# konekobit-001.net
KiCad netlist of a schematic drawn in EAGLE
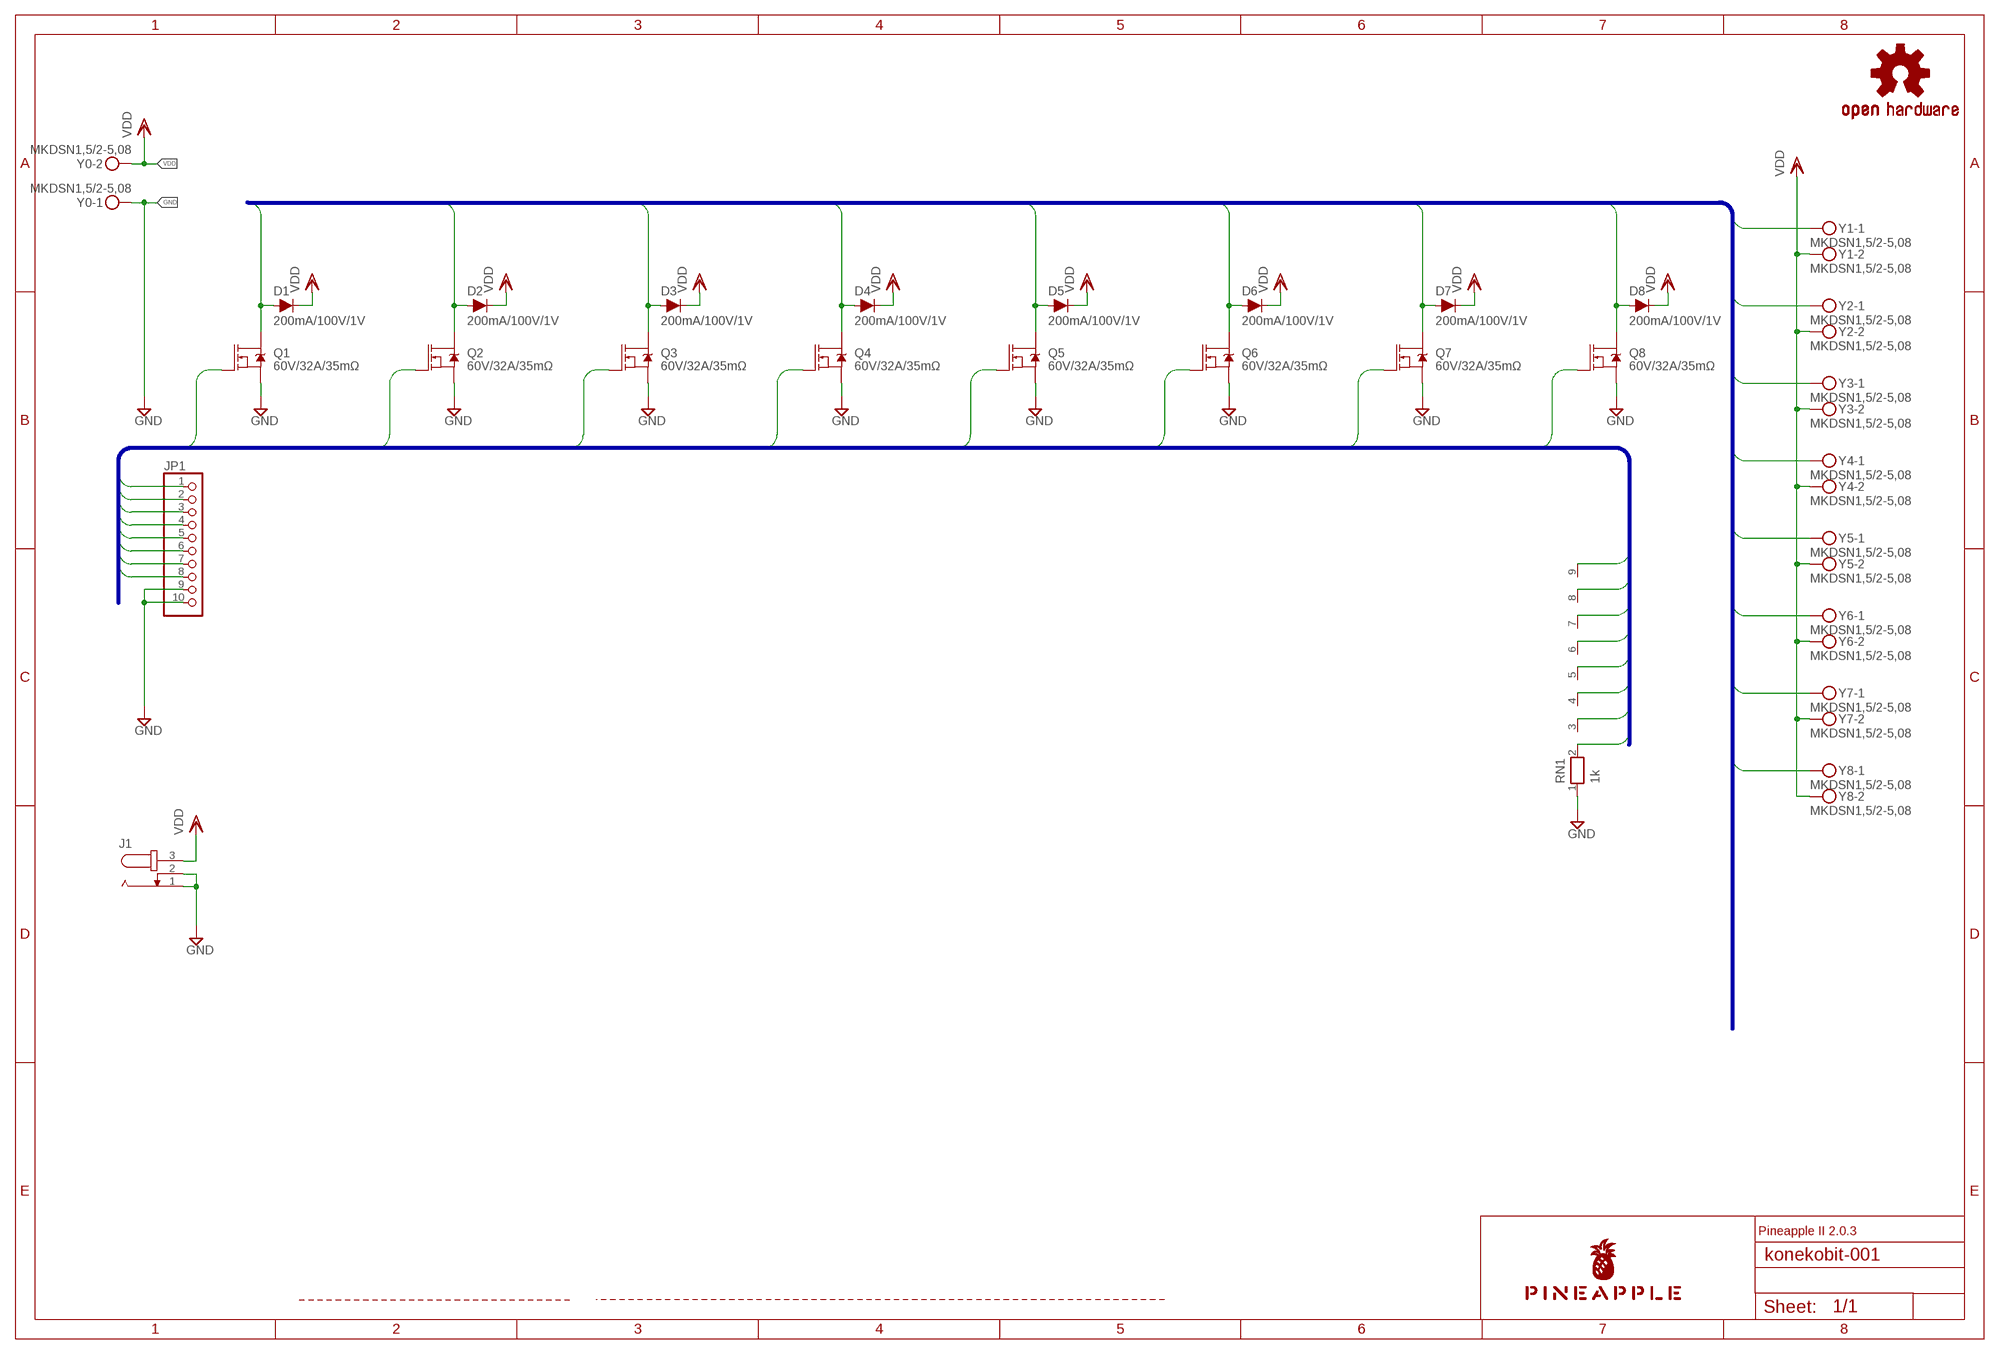
[diagram p0: schematic, sheet 1]

(export (version "E")
  (design (tool "Eeschema 10.0.6"))
  (components
    (comp (ref "D1")
      (value "200mA/100V/1V")
      (footprint "eagle-import:DIODE-1N4148")
      (libsource (lib "eagle-import") (part "DIODE-1N4148"))
    )
    (comp (ref "D2")
      (value "200mA/100V/1V")
      (footprint "eagle-import:DIODE-1N4148")
      (libsource (lib "eagle-import") (part "DIODE-1N4148"))
    )
    (comp (ref "D3")
      (value "200mA/100V/1V")
      (footprint "eagle-import:DIODE-1N4148")
      (libsource (lib "eagle-import") (part "DIODE-1N4148"))
    )
    (comp (ref "D4")
      (value "200mA/100V/1V")
      (footprint "eagle-import:DIODE-1N4148")
      (libsource (lib "eagle-import") (part "DIODE-1N4148"))
    )
    (comp (ref "D5")
      (value "200mA/100V/1V")
      (footprint "eagle-import:DIODE-1N4148")
      (libsource (lib "eagle-import") (part "DIODE-1N4148"))
    )
    (comp (ref "D6")
      (value "200mA/100V/1V")
      (footprint "eagle-import:DIODE-1N4148")
      (libsource (lib "eagle-import") (part "DIODE-1N4148"))
    )
    (comp (ref "D7")
      (value "200mA/100V/1V")
      (footprint "eagle-import:DIODE-1N4148")
      (libsource (lib "eagle-import") (part "DIODE-1N4148"))
    )
    (comp (ref "D8")
      (value "200mA/100V/1V")
      (footprint "eagle-import:DIODE-1N4148")
      (libsource (lib "eagle-import") (part "DIODE-1N4148"))
    )
    (comp (ref "J1")
      (value "JACK-PLUG0")
      (footprint "eagle-import:SPC4077")
      (libsource (lib "eagle-import") (part "JACK-PLUG0"))
    )
    (comp (ref "JP1")
      (value "PINHD-1X10")
      (footprint "eagle-import:1X10")
      (libsource (lib "eagle-import") (part "PINHD-1X10"))
    )
    (comp (ref "LOGO1")
      (value "OSHW-LOGOS-COPPER")
      (footprint "eagle-import:OSHW-LOGO-S_COPPER")
      (libsource (lib "eagle-import") (part "OSHW-LOGOS-COPPER"))
    )
    (comp (ref "Q1")
      (value "60V/32A/35mΩ")
      (footprint "eagle-import:TO220V")
      (libsource (lib "eagle-import") (part "MOSFET-NCH-FQP30N06L"))
    )
    (comp (ref "Q2")
      (value "60V/32A/35mΩ")
      (footprint "eagle-import:TO220V")
      (libsource (lib "eagle-import") (part "MOSFET-NCH-FQP30N06L"))
    )
    (comp (ref "Q3")
      (value "60V/32A/35mΩ")
      (footprint "eagle-import:TO220V")
      (libsource (lib "eagle-import") (part "MOSFET-NCH-FQP30N06L"))
    )
    (comp (ref "Q4")
      (value "60V/32A/35mΩ")
      (footprint "eagle-import:TO220V")
      (libsource (lib "eagle-import") (part "MOSFET-NCH-FQP30N06L"))
    )
    (comp (ref "Q5")
      (value "60V/32A/35mΩ")
      (footprint "eagle-import:TO220V")
      (libsource (lib "eagle-import") (part "MOSFET-NCH-FQP30N06L"))
    )
    (comp (ref "Q6")
      (value "60V/32A/35mΩ")
      (footprint "eagle-import:TO220V")
      (libsource (lib "eagle-import") (part "MOSFET-NCH-FQP30N06L"))
    )
    (comp (ref "Q7")
      (value "60V/32A/35mΩ")
      (footprint "eagle-import:TO220V")
      (libsource (lib "eagle-import") (part "MOSFET-NCH-FQP30N06L"))
    )
    (comp (ref "Q8")
      (value "60V/32A/35mΩ")
      (footprint "eagle-import:TO220V")
      (libsource (lib "eagle-import") (part "MOSFET-NCH-FQP30N06L"))
    )
    (comp (ref "RN1")
      (value "1k")
      (footprint "eagle-import:RN-9")
      (libsource (lib "eagle-import") (part "RN08"))
    )
    (comp (ref "U$1")
      (value "PINEAPPLE450_SILK")
      (footprint "eagle-import:PINEAPPLE450_SILK")
      (libsource (lib "eagle-import") (part "PINEAPPLE450_SILK"))
    )
    (comp (ref "Y0")
      (value "MKDSN1,5/2-5,08")
      (footprint "eagle-import:MKDSN1,5_2-5,08")
      (libsource (lib "eagle-import") (part "MKDSN1,5/2-5,08"))
    )
    (comp (ref "Y1")
      (value "MKDSN1,5/2-5,08")
      (footprint "eagle-import:MKDSN1,5_2-5,08")
      (libsource (lib "eagle-import") (part "MKDSN1,5/2-5,08"))
    )
    (comp (ref "Y2")
      (value "MKDSN1,5/2-5,08")
      (footprint "eagle-import:MKDSN1,5_2-5,08")
      (libsource (lib "eagle-import") (part "MKDSN1,5/2-5,08"))
    )
    (comp (ref "Y3")
      (value "MKDSN1,5/2-5,08")
      (footprint "eagle-import:MKDSN1,5_2-5,08")
      (libsource (lib "eagle-import") (part "MKDSN1,5/2-5,08"))
    )
    (comp (ref "Y4")
      (value "MKDSN1,5/2-5,08")
      (footprint "eagle-import:MKDSN1,5_2-5,08")
      (libsource (lib "eagle-import") (part "MKDSN1,5/2-5,08"))
    )
    (comp (ref "Y5")
      (value "MKDSN1,5/2-5,08")
      (footprint "eagle-import:MKDSN1,5_2-5,08")
      (libsource (lib "eagle-import") (part "MKDSN1,5/2-5,08"))
    )
    (comp (ref "Y6")
      (value "MKDSN1,5/2-5,08")
      (footprint "eagle-import:MKDSN1,5_2-5,08")
      (libsource (lib "eagle-import") (part "MKDSN1,5/2-5,08"))
    )
    (comp (ref "Y7")
      (value "MKDSN1,5/2-5,08")
      (footprint "eagle-import:MKDSN1,5_2-5,08")
      (libsource (lib "eagle-import") (part "MKDSN1,5/2-5,08"))
    )
    (comp (ref "Y8")
      (value "MKDSN1,5/2-5,08")
      (footprint "eagle-import:MKDSN1,5_2-5,08")
      (libsource (lib "eagle-import") (part "MKDSN1,5/2-5,08"))
    )
  )
  (nets
    (net (code "1") (name "/DRAIN1") (class "Default")
      (node (ref "D1") (pin "A") (pinfunction "A_A") (pintype "passive"))
      (node (ref "Q1") (pin "2") (pinfunction "D_2") (pintype "bidirectional"))
      (node (ref "Y1") (pin "1") (pinfunction "KL_1") (pintype "passive"))
    )
    (net (code "2") (name "/DRAIN2") (class "Default")
      (node (ref "D2") (pin "A") (pinfunction "A_A") (pintype "passive"))
      (node (ref "Q2") (pin "2") (pinfunction "D_2") (pintype "bidirectional"))
      (node (ref "Y2") (pin "1") (pinfunction "KL_1") (pintype "passive"))
    )
    (net (code "3") (name "/DRAIN3") (class "Default")
      (node (ref "D3") (pin "A") (pinfunction "A_A") (pintype "passive"))
      (node (ref "Q3") (pin "2") (pinfunction "D_2") (pintype "bidirectional"))
      (node (ref "Y3") (pin "1") (pinfunction "KL_1") (pintype "passive"))
    )
    (net (code "4") (name "/DRAIN4") (class "Default")
      (node (ref "D4") (pin "A") (pinfunction "A_A") (pintype "passive"))
      (node (ref "Q4") (pin "2") (pinfunction "D_2") (pintype "bidirectional"))
      (node (ref "Y4") (pin "1") (pinfunction "KL_1") (pintype "passive"))
    )
    (net (code "5") (name "/DRAIN5") (class "Default")
      (node (ref "D5") (pin "A") (pinfunction "A_A") (pintype "passive"))
      (node (ref "Q5") (pin "2") (pinfunction "D_2") (pintype "bidirectional"))
      (node (ref "Y5") (pin "1") (pinfunction "KL_1") (pintype "passive"))
    )
    (net (code "6") (name "/DRAIN6") (class "Default")
      (node (ref "D6") (pin "A") (pinfunction "A_A") (pintype "passive"))
      (node (ref "Q6") (pin "2") (pinfunction "D_2") (pintype "bidirectional"))
      (node (ref "Y6") (pin "1") (pinfunction "KL_1") (pintype "passive"))
    )
    (net (code "7") (name "/DRAIN7") (class "Default")
      (node (ref "D7") (pin "A") (pinfunction "A_A") (pintype "passive"))
      (node (ref "Q7") (pin "2") (pinfunction "D_2") (pintype "bidirectional"))
      (node (ref "Y7") (pin "1") (pinfunction "KL_1") (pintype "passive"))
    )
    (net (code "8") (name "/DRAIN8") (class "Default")
      (node (ref "D8") (pin "A") (pinfunction "A_A") (pintype "passive"))
      (node (ref "Q8") (pin "2") (pinfunction "D_2") (pintype "bidirectional"))
      (node (ref "Y8") (pin "1") (pinfunction "KL_1") (pintype "passive"))
    )
    (net (code "9") (name "/PWM1") (class "Default")
      (node (ref "JP1") (pin "1") (pinfunction "1_1") (pintype "passive"))
      (node (ref "Q1") (pin "1") (pinfunction "G_1") (pintype "bidirectional"))
      (node (ref "RN1") (pin "2") (pinfunction "2_2") (pintype "passive"))
    )
    (net (code "10") (name "/PWM2") (class "Default")
      (node (ref "JP1") (pin "2") (pinfunction "2_2") (pintype "passive"))
      (node (ref "Q2") (pin "1") (pinfunction "G_1") (pintype "bidirectional"))
      (node (ref "RN1") (pin "3") (pinfunction "3_3") (pintype "passive"))
    )
    (net (code "11") (name "/PWM3") (class "Default")
      (node (ref "JP1") (pin "3") (pinfunction "3_3") (pintype "passive"))
      (node (ref "Q3") (pin "1") (pinfunction "G_1") (pintype "bidirectional"))
      (node (ref "RN1") (pin "4") (pinfunction "4_4") (pintype "passive"))
    )
    (net (code "12") (name "/PWM4") (class "Default")
      (node (ref "JP1") (pin "4") (pinfunction "4_4") (pintype "passive"))
      (node (ref "Q4") (pin "1") (pinfunction "G_1") (pintype "bidirectional"))
      (node (ref "RN1") (pin "5") (pinfunction "5_5") (pintype "passive"))
    )
    (net (code "13") (name "/PWM5") (class "Default")
      (node (ref "JP1") (pin "5") (pinfunction "5_5") (pintype "passive"))
      (node (ref "Q5") (pin "1") (pinfunction "G_1") (pintype "bidirectional"))
      (node (ref "RN1") (pin "6") (pinfunction "6_6") (pintype "passive"))
    )
    (net (code "14") (name "/PWM6") (class "Default")
      (node (ref "JP1") (pin "6") (pinfunction "6_6") (pintype "passive"))
      (node (ref "Q6") (pin "1") (pinfunction "G_1") (pintype "bidirectional"))
      (node (ref "RN1") (pin "7") (pinfunction "7_7") (pintype "passive"))
    )
    (net (code "15") (name "/PWM7") (class "Default")
      (node (ref "JP1") (pin "7") (pinfunction "7_7") (pintype "passive"))
      (node (ref "Q7") (pin "1") (pinfunction "G_1") (pintype "bidirectional"))
      (node (ref "RN1") (pin "8") (pinfunction "8_8") (pintype "passive"))
    )
    (net (code "16") (name "/PWM8") (class "Default")
      (node (ref "JP1") (pin "8") (pinfunction "8_8") (pintype "passive"))
      (node (ref "Q8") (pin "1") (pinfunction "G_1") (pintype "bidirectional"))
      (node (ref "RN1") (pin "9") (pinfunction "9_9") (pintype "passive"))
    )
    (net (code "17") (name "GND") (class "Default")
      (node (ref "J1") (pin "1") (pinfunction "1_1") (pintype "passive"))
      (node (ref "J1") (pin "2") (pinfunction "2_2") (pintype "passive"))
      (node (ref "JP1") (pin "10") (pinfunction "10_10") (pintype "passive"))
      (node (ref "JP1") (pin "9") (pinfunction "9_9") (pintype "passive"))
      (node (ref "Q1") (pin "3") (pinfunction "S_3") (pintype "bidirectional"))
      (node (ref "Q2") (pin "3") (pinfunction "S_3") (pintype "bidirectional"))
      (node (ref "Q3") (pin "3") (pinfunction "S_3") (pintype "bidirectional"))
      (node (ref "Q4") (pin "3") (pinfunction "S_3") (pintype "bidirectional"))
      (node (ref "Q5") (pin "3") (pinfunction "S_3") (pintype "bidirectional"))
      (node (ref "Q6") (pin "3") (pinfunction "S_3") (pintype "bidirectional"))
      (node (ref "Q7") (pin "3") (pinfunction "S_3") (pintype "bidirectional"))
      (node (ref "Q8") (pin "3") (pinfunction "S_3") (pintype "bidirectional"))
      (node (ref "RN1") (pin "1") (pinfunction "1_1") (pintype "passive"))
      (node (ref "Y0") (pin "1") (pinfunction "KL_1") (pintype "passive"))
    )
    (net (code "18") (name "VDD") (class "Default")
      (node (ref "D1") (pin "C") (pinfunction "C_C") (pintype "passive"))
      (node (ref "D2") (pin "C") (pinfunction "C_C") (pintype "passive"))
      (node (ref "D3") (pin "C") (pinfunction "C_C") (pintype "passive"))
      (node (ref "D4") (pin "C") (pinfunction "C_C") (pintype "passive"))
      (node (ref "D5") (pin "C") (pinfunction "C_C") (pintype "passive"))
      (node (ref "D6") (pin "C") (pinfunction "C_C") (pintype "passive"))
      (node (ref "D7") (pin "C") (pinfunction "C_C") (pintype "passive"))
      (node (ref "D8") (pin "C") (pinfunction "C_C") (pintype "passive"))
      (node (ref "J1") (pin "3") (pinfunction "3_3") (pintype "passive"))
      (node (ref "Y0") (pin "2") (pinfunction "KL_2") (pintype "passive"))
      (node (ref "Y1") (pin "2") (pinfunction "KL_2") (pintype "passive"))
      (node (ref "Y2") (pin "2") (pinfunction "KL_2") (pintype "passive"))
      (node (ref "Y3") (pin "2") (pinfunction "KL_2") (pintype "passive"))
      (node (ref "Y4") (pin "2") (pinfunction "KL_2") (pintype "passive"))
      (node (ref "Y5") (pin "2") (pinfunction "KL_2") (pintype "passive"))
      (node (ref "Y6") (pin "2") (pinfunction "KL_2") (pintype "passive"))
      (node (ref "Y7") (pin "2") (pinfunction "KL_2") (pintype "passive"))
      (node (ref "Y8") (pin "2") (pinfunction "KL_2") (pintype "passive"))
    )
  )
)
